# gloBrdA.net
KiCad netlist of a schematic drawn in EAGLE
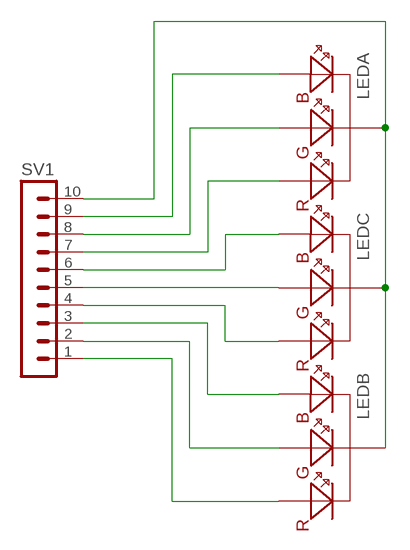
[diagram p0: schematic, sheet 1]

(export (version "E")
  (design (tool "Eeschema 10.0.6"))
  (components
    (comp (ref "LEDA")
      (value "MULTICOLORLED")
      (footprint "eagle-import:MULTICOLORLED")
      (libsource (lib "eagle-import") (part "MULTICOLORLED"))
    )
    (comp (ref "LEDB")
      (value "MULTICOLORLED")
      (footprint "eagle-import:MULTICOLORLED")
      (libsource (lib "eagle-import") (part "MULTICOLORLED"))
    )
    (comp (ref "LEDC")
      (value "MULTICOLORLED")
      (footprint "eagle-import:MULTICOLORLED")
      (libsource (lib "eagle-import") (part "MULTICOLORLED"))
    )
    (comp (ref "SV1")
      (value "MA10-1")
      (footprint "eagle-import:MA10-1")
      (libsource (lib "eagle-import") (part "MA10-1"))
    )
  )
  (nets
    (net (code "1") (name "Net-(LEDA-PadGND)") (class "Default")
      (node (ref "LEDA") (pin "GND") (pinfunction "GND_GND") (pintype "bidirectional"))
      (node (ref "LEDB") (pin "GND") (pinfunction "GND_GND") (pintype "bidirectional"))
      (node (ref "LEDC") (pin "GND") (pinfunction "GND_GND") (pintype "bidirectional"))
      (node (ref "SV1") (pin "10") (pinfunction "10_10") (pintype "passive"))
    )
    (net (code "2") (name "Net-(LEDA-PadLED-B)") (class "Default")
      (node (ref "LEDA") (pin "LED-B") (pinfunction "LED-B_LED-B") (pintype "bidirectional"))
      (node (ref "SV1") (pin "9") (pinfunction "9_9") (pintype "passive"))
    )
    (net (code "3") (name "Net-(LEDA-PadLED-G)") (class "Default")
      (node (ref "LEDA") (pin "LED-G") (pinfunction "LED-G_LED-G") (pintype "bidirectional"))
      (node (ref "SV1") (pin "8") (pinfunction "8_8") (pintype "passive"))
    )
    (net (code "4") (name "Net-(LEDA-PadLED-R)") (class "Default")
      (node (ref "LEDA") (pin "LED-R") (pinfunction "LED-R_LED-R") (pintype "bidirectional"))
      (node (ref "SV1") (pin "7") (pinfunction "7_7") (pintype "passive"))
    )
    (net (code "5") (name "Net-(LEDB-PadLED-B)") (class "Default")
      (node (ref "LEDB") (pin "LED-B") (pinfunction "LED-B_LED-B") (pintype "bidirectional"))
      (node (ref "SV1") (pin "3") (pinfunction "3_3") (pintype "passive"))
    )
    (net (code "6") (name "Net-(LEDB-PadLED-G)") (class "Default")
      (node (ref "LEDB") (pin "LED-G") (pinfunction "LED-G_LED-G") (pintype "bidirectional"))
      (node (ref "SV1") (pin "2") (pinfunction "2_2") (pintype "passive"))
    )
    (net (code "7") (name "Net-(LEDB-PadLED-R)") (class "Default")
      (node (ref "LEDB") (pin "LED-R") (pinfunction "LED-R_LED-R") (pintype "bidirectional"))
      (node (ref "SV1") (pin "1") (pinfunction "1_1") (pintype "passive"))
    )
    (net (code "8") (name "Net-(LEDC-PadLED-B)") (class "Default")
      (node (ref "LEDC") (pin "LED-B") (pinfunction "LED-B_LED-B") (pintype "bidirectional"))
      (node (ref "SV1") (pin "6") (pinfunction "6_6") (pintype "passive"))
    )
    (net (code "9") (name "Net-(LEDC-PadLED-G)") (class "Default")
      (node (ref "LEDC") (pin "LED-G") (pinfunction "LED-G_LED-G") (pintype "bidirectional"))
      (node (ref "SV1") (pin "5") (pinfunction "5_5") (pintype "passive"))
    )
    (net (code "10") (name "Net-(LEDC-PadLED-R)") (class "Default")
      (node (ref "LEDC") (pin "LED-R") (pinfunction "LED-R_LED-R") (pintype "bidirectional"))
      (node (ref "SV1") (pin "4") (pinfunction "4_4") (pintype "passive"))
    )
  )
)
